# ball_catch_sensor_1.net
KiCad netlist of a schematic drawn in EAGLE
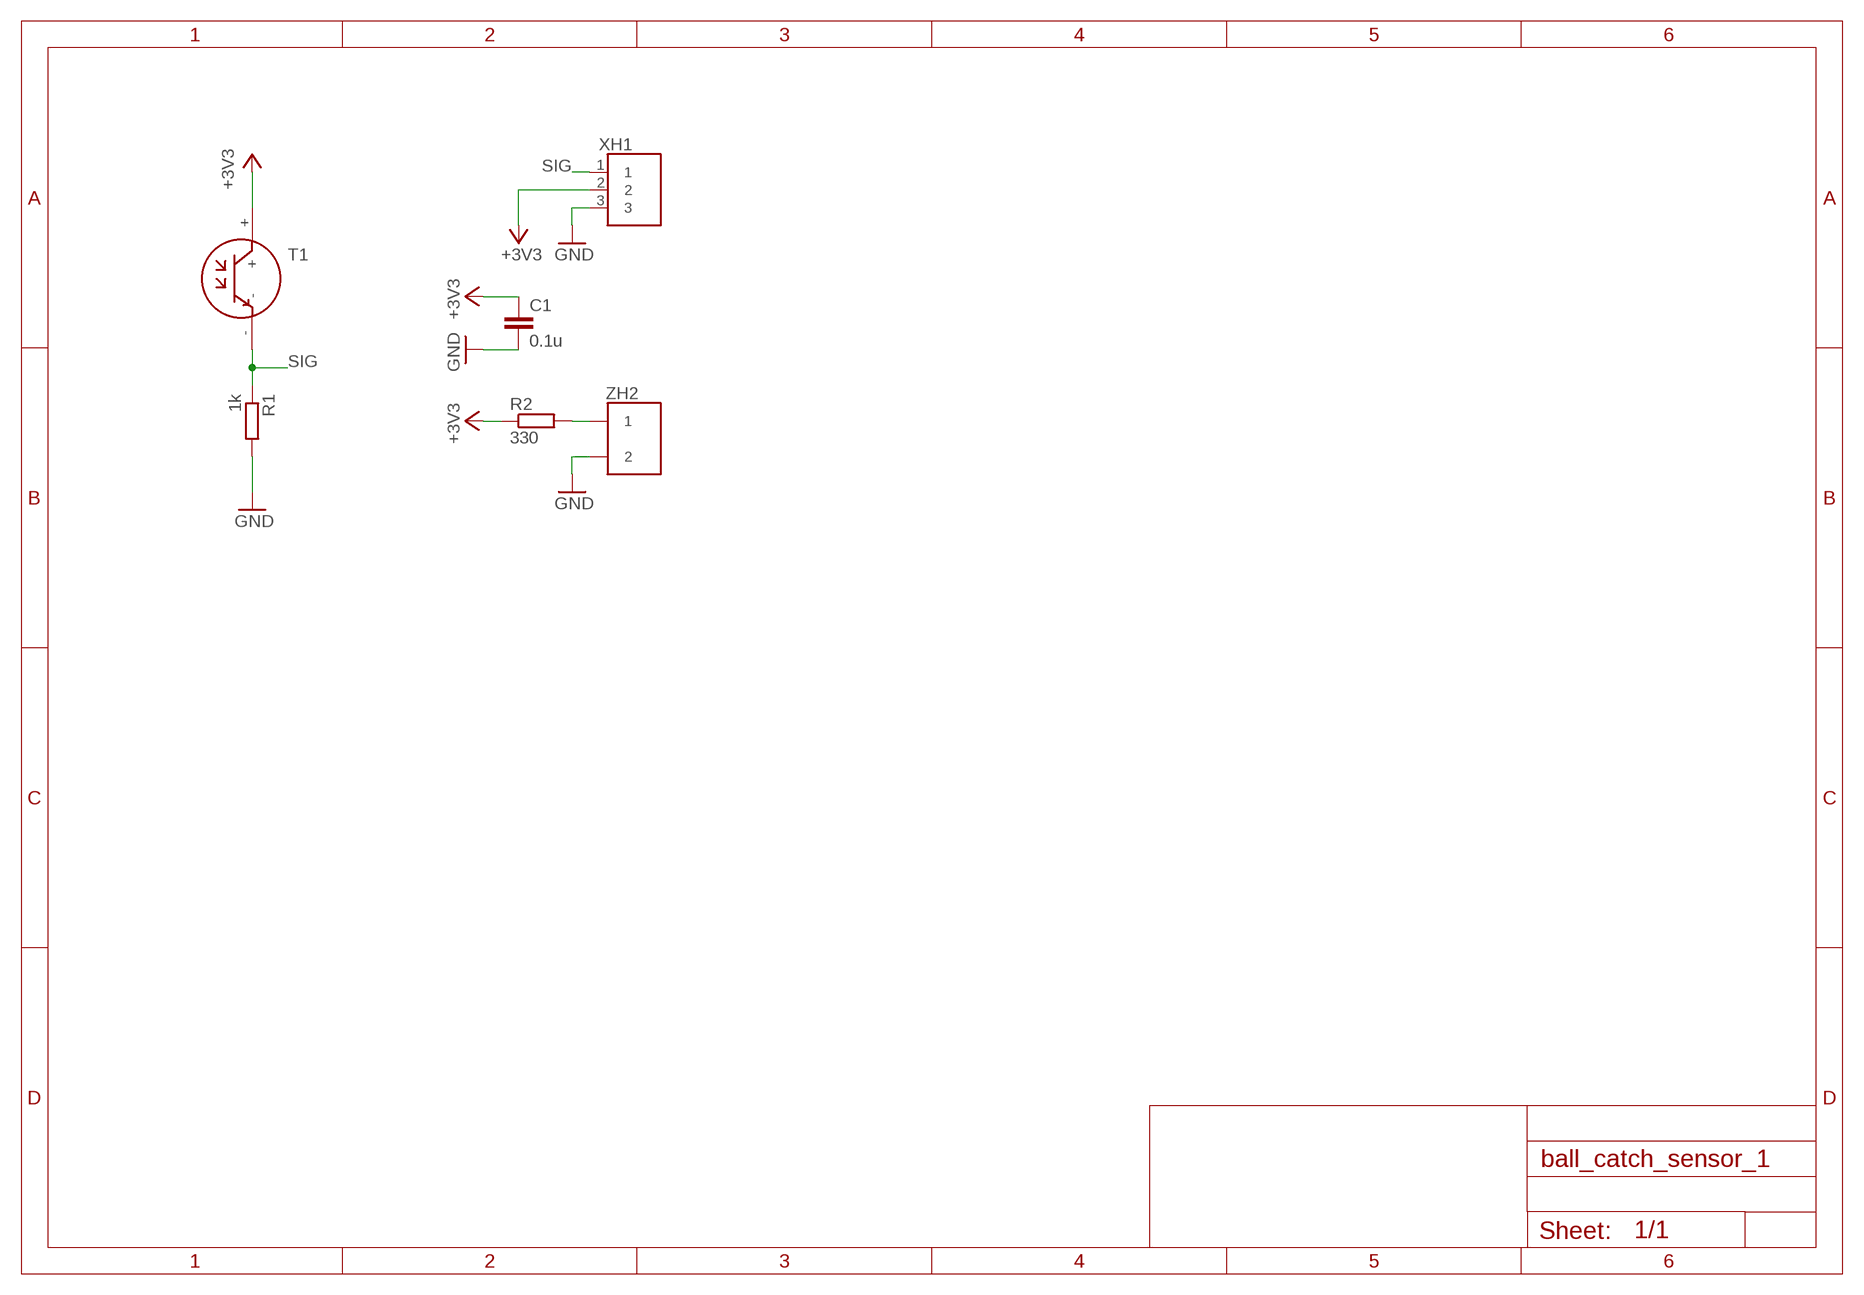
[diagram p0: schematic, sheet 1]

(export (version "E")
  (design (tool "Eeschema 10.0.6"))
  (components
    (comp (ref "C1")
      (value "0.1u")
      (footprint "eagle-import:C0603")
      (libsource (lib "eagle-import") (part "C-EUC0603"))
    )
    (comp (ref "R1")
      (value "1k")
      (footprint "eagle-import:0207_10")
      (libsource (lib "eagle-import") (part "R-EU_0207/10"))
    )
    (comp (ref "R2")
      (value "330")
      (footprint "eagle-import:0207_10")
      (libsource (lib "eagle-import") (part "R-EU_0207/10"))
    )
    (comp (ref "T1")
      (value "NJL7302L-F3")
      (footprint "eagle-import:NJL7302L-F3")
      (libsource (lib "eagle-import") (part "NJL7302L-F3"))
    )
    (comp (ref "XH1")
      (value "S3B")
      (footprint "eagle-import:S3B")
      (libsource (lib "eagle-import") (part "S3B"))
    )
    (comp (ref "ZH2") (value "2B") (footprint "eagle-import:2B") (libsource (lib "eagle-import") (part "2B")))
  )
  (nets
    (net (code "1") (name "+3V3") (class "Default")
      (node (ref "C1") (pin "1") (pinfunction "1_1") (pintype "passive"))
      (node (ref "R2") (pin "1") (pinfunction "1_1") (pintype "passive"))
      (node (ref "T1") (pin "+") (pinfunction "+_+") (pintype "bidirectional"))
      (node (ref "XH1") (pin "2") (pinfunction "2_2") (pintype "bidirectional"))
    )
    (net (code "2") (name "/SIG") (class "Default")
      (node (ref "R1") (pin "1") (pinfunction "1_1") (pintype "passive"))
      (node (ref "T1") (pin "-") (pinfunction "-_-") (pintype "bidirectional"))
      (node (ref "XH1") (pin "1") (pinfunction "1_1") (pintype "bidirectional"))
    )
    (net (code "3") (name "GND") (class "Default")
      (node (ref "C1") (pin "2") (pinfunction "2_2") (pintype "passive"))
      (node (ref "R1") (pin "2") (pinfunction "2_2") (pintype "passive"))
      (node (ref "XH1") (pin "3") (pinfunction "3_3") (pintype "bidirectional"))
      (node (ref "ZH2") (pin "2") (pinfunction "2_2") (pintype "bidirectional"))
    )
    (net (code "4") (name "Net-(R2-Pad2)") (class "Default")
      (node (ref "R2") (pin "2") (pinfunction "2_2") (pintype "passive"))
      (node (ref "ZH2") (pin "1") (pinfunction "1_1") (pintype "bidirectional"))
    )
  )
)
